# PMUIO_BLOCK.net
KiCad netlist of a schematic drawn in Altium Designer
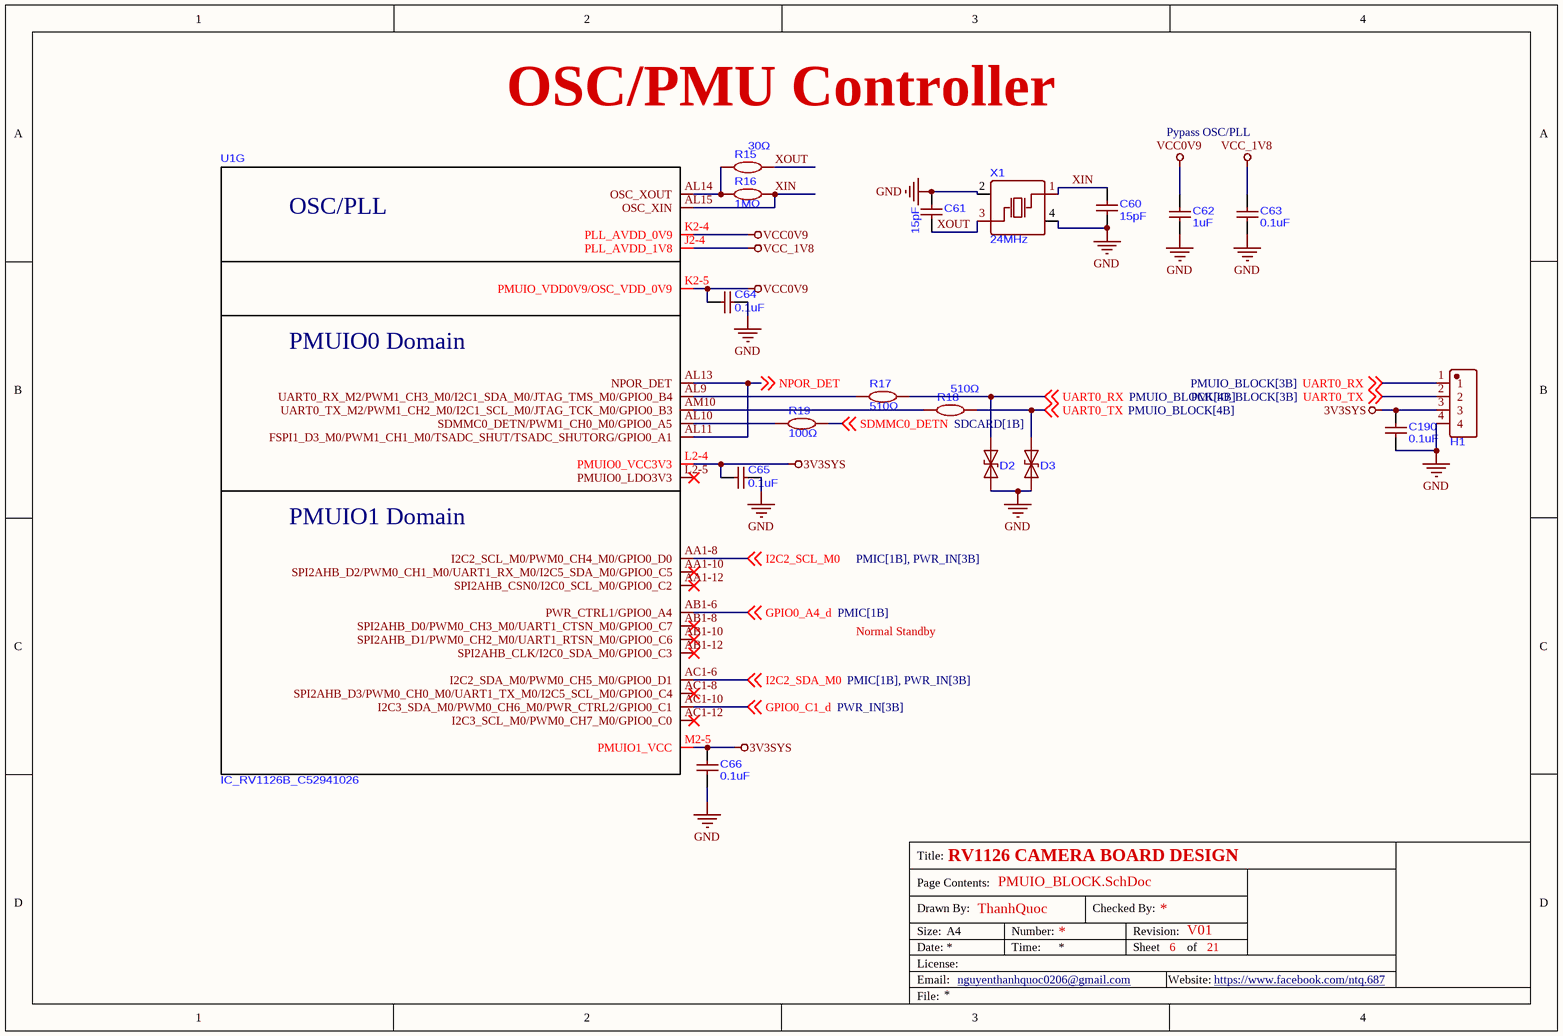
[diagram p0: PMUIO_BLOCK.SchDoc]

(export (version "E")
  (design (tool "Eeschema 10.0.6"))
  (components
    (comp (ref "C60")
      (value "15pF")
      (footprint "C0201")
      (description "CAP CER 15pF 50V NP0 0201")
      (libsource (lib "Schlib1") (part "CAP_15pF-25V-5%-0201"))
    )
    (comp (ref "C61")
      (value "15pF")
      (footprint "C0201")
      (description "CAP CER 15pF 50V NP0 0201")
      (libsource (lib "Schlib1") (part "CAP_15pF-25V-5%-0201"))
    )
    (comp (ref "C62")
      (value "1uF")
      (footprint "C0201")
      (description "1uF ±10% 6.3V Ceramic Capacitor X5R 0201")
      (libsource (lib "Schlib1") (part "CAP_1uF-6.3V-10%-0201"))
    )
    (comp (ref "C63")
      (value "0.1uF")
      (footprint "C0201")
      (description "0.1uF ±10% 6.3V Ceramic Capacitor X5R 0201")
      (libsource (lib "Schlib1") (part "CAP_100nF-6.3V-10%-0201_1"))
    )
    (comp (ref "C64")
      (value "0.1uF")
      (footprint "C0201")
      (description "0.1uF ±10% 6.3V Ceramic Capacitor X5R 0201")
      (libsource (lib "Schlib1") (part "CAP_100nF-6.3V-10%-0201_1"))
    )
    (comp (ref "C65")
      (value "0.1uF")
      (footprint "C0201")
      (description "0.1uF ±10% 6.3V Ceramic Capacitor X5R 0201")
      (libsource (lib "Schlib1") (part "CAP_100nF-6.3V-10%-0201_1"))
    )
    (comp (ref "C66")
      (value "0.1uF")
      (footprint "C0201")
      (description "0.1uF ±10% 6.3V Ceramic Capacitor X5R 0201")
      (libsource (lib "Schlib1") (part "CAP_100nF-6.3V-10%-0201_1"))
    )
    (comp (ref "C190")
      (value "0.1uF")
      (footprint "C0201")
      (description "0.1uF ±10% 6.3V Ceramic Capacitor X5R 0201")
      (libsource (lib "Schlib1") (part "CAP_100nF-6.3V-10%-0201_1"))
    )
    (comp (ref "D2")
      (value "ESD DIODE")
      (footprint "DSN0603-2_L0.7-W0.3-P0.40-BI")
      (description "ESD DIODE 5VWM 5VC DSN0603-2 0.13PF")
      (libsource (lib "Schlib1") (part "PESD5V0H1BSFYL"))
    )
    (comp (ref "D3")
      (value "ESD DIODE")
      (footprint "DSN0603-2_L0.7-W0.3-P0.40-BI")
      (description "ESD DIODE 5VWM 5VC DSN0603-2 0.13PF")
      (libsource (lib "Schlib1") (part "PESD5V0H1BSFYL"))
    )
    (comp (ref "H1")
      (value "Through Hole,P=1.27mm")
      (footprint "HDR-TH_4P-P1.27-V-M")
      (libsource (lib "Schlib1") (part "PZ127V-11-04-0720"))
    )
    (comp (ref "R15")
      (value "30Ω")
      (footprint "R0201")
      (description "RES 30Ω ±1% 50mW 0201")
      (libsource (lib "Schlib1") (part "RES_30Ω-0.05W-1%-0201"))
    )
    (comp (ref "R16")
      (value "1MΩ")
      (footprint "R0201")
      (description "RES 1MΩ ±5% 50mW 0201")
      (libsource (lib "Schlib1") (part "RES_1M-0.1W-5%-0201"))
    )
    (comp (ref "R17")
      (value "510Ω")
      (footprint "R0201")
      (description "510Ω 50mW 25V Thick Film Resistor ±200ppm/℃ ±1% 0201 Chip Resistor - Surface Mount RoHS")
      (libsource (lib "Schlib1") (part "RES_510-0.05W-1%-0201"))
    )
    (comp (ref "R18")
      (value "510Ω")
      (footprint "R0201")
      (description "510Ω 50mW 25V Thick Film Resistor ±200ppm/℃ ±1% 0201 Chip Resistor - Surface Mount RoHS")
      (libsource (lib "Schlib1") (part "RES_510-0.05W-1%-0201"))
    )
    (comp (ref "R19")
      (value "100Ω")
      (footprint "R0201")
      (description "RES 100Ω ±1% 50mW 0201")
      (libsource (lib "Schlib1") (part "RES_100OHM-50mW-1%-0201"))
    )
    (comp (ref "U1")
      (value "IC_RV1126B_C52941026")
      (footprint "CCSP-491_L14.0-W14.0-TL_RV1126B")
      (libsource (lib "Schlib1") (part "IC_RV1126B_C52941026"))
    )
    (comp (ref "X1")
      (value "24MHz")
      (footprint "CRYSTAL-SMD_4P-L2.0-W1.6-BL")
      (description "CRYSTAL 24MHz 12pF SMD")
      (libsource (lib "Schlib1") (part "XTAL_24Mhz-12pF-4-SMD"))
    )
  )
  (nets
    (net (code "1") (name "/XIN") (class "Default")
      (node (ref "C60") (pin "2") (pinfunction "2_2") (pintype "passive"))
      (node (ref "R16") (pin "2") (pinfunction "2_2") (pintype "passive"))
      (node (ref "U1") (pin "AL15") (pinfunction "OSC_XIN_AL15") (pintype "passive"))
      (node (ref "X1") (pin "1") (pinfunction "OSC1_1") (pintype "passive"))
    )
    (net (code "2") (name "/XOUT") (class "Default")
      (node (ref "C61") (pin "1") (pinfunction "1_1") (pintype "passive"))
      (node (ref "R15") (pin "2") (pinfunction "2_2") (pintype "passive"))
      (node (ref "X1") (pin "3") (pinfunction "OSC2_3") (pintype "passive"))
    )
    (net (code "3") (name "3V3SYS") (class "Default")
      (node (ref "C190") (pin "2") (pinfunction "2_2") (pintype "passive"))
      (node (ref "C65") (pin "2") (pinfunction "2_2") (pintype "passive"))
      (node (ref "C66") (pin "2") (pinfunction "2_2") (pintype "passive"))
      (node (ref "H1") (pin "3") (pinfunction "3_3") (pintype "passive"))
      (node (ref "U1") (pin "L2-4") (pinfunction "PMUIO0_VCC3V3_L2-4") (pintype "passive"))
      (node (ref "U1") (pin "M2-5") (pinfunction "PMUIO1_VCC_M2-5") (pintype "passive"))
    )
    (net (code "4") (name "GND") (class "Default")
      (node (ref "C190") (pin "1") (pinfunction "1_1") (pintype "passive"))
      (node (ref "C60") (pin "1") (pinfunction "1_1") (pintype "passive"))
      (node (ref "C61") (pin "2") (pinfunction "2_2") (pintype "passive"))
      (node (ref "C62") (pin "1") (pinfunction "1_1") (pintype "passive"))
      (node (ref "C63") (pin "1") (pinfunction "1_1") (pintype "passive"))
      (node (ref "C64") (pin "1") (pinfunction "1_1") (pintype "passive"))
      (node (ref "C65") (pin "1") (pinfunction "1_1") (pintype "passive"))
      (node (ref "C66") (pin "1") (pinfunction "1_1") (pintype "passive"))
      (node (ref "D2") (pin "1") (pinfunction "K_1") (pintype "passive"))
      (node (ref "D3") (pin "1") (pinfunction "K_1") (pintype "passive"))
      (node (ref "H1") (pin "4") (pinfunction "4_4") (pintype "passive"))
      (node (ref "X1") (pin "2") (pinfunction "GND_2") (pintype "passive"))
      (node (ref "X1") (pin "4") (pinfunction "GND_4") (pintype "passive"))
    )
    (net (code "5") (name "GPIO0_A4_d") (class "Default")
      (node (ref "U1") (pin "AB1-6") (pinfunction "PWR_CTRL1/GPIO0_A4_AB1-6") (pintype "passive"))
    )
    (net (code "6") (name "GPIO0_C1_d") (class "Default")
      (node (ref "U1") (pin "AC1-10") (pinfunction "I2C3_SDA_M0/PWM0_CH6_M0/PWR_CTRL2/GPIO0_C1_AC1-10") (pintype "passive"))
    )
    (net (code "7") (name "I2C2_SCL_M0") (class "Default")
      (node (ref "U1") (pin "AA1-8") (pinfunction "I2C2_SCL_M0/PWM0_CH4_M0/GPIO0_D0_AA1-8") (pintype "passive"))
    )
    (net (code "8") (name "I2C2_SDA_M0") (class "Default")
      (node (ref "U1") (pin "AC1-6") (pinfunction "I2C2_SDA_M0/PWM0_CH5_M0/GPIO0_D1_AC1-6") (pintype "passive"))
    )
    (net (code "9") (name "NPOR_DET") (class "Default")
      (node (ref "U1") (pin "AL11") (pinfunction "FSPI1_D3_M0/PWM1_CH1_M0/TSADC_SHUT/TSADC_SHUTORG/GPIO0_A1_AL11") (pintype "passive"))
      (node (ref "U1") (pin "AL13") (pinfunction "NPOR_DET_AL13") (pintype "passive"))
    )
    (net (code "10") (name "Net-(U1G-OSC_XOUT)") (class "Default")
      (node (ref "R15") (pin "1") (pinfunction "1_1") (pintype "passive"))
      (node (ref "R16") (pin "1") (pinfunction "1_1") (pintype "passive"))
      (node (ref "U1") (pin "AL14") (pinfunction "OSC_XOUT_AL14") (pintype "passive"))
    )
    (net (code "11") (name "Net-(U1G-SDMMC0_DETN{slash}PWM1_CH0_M0{slash}GPIO0_A5)") (class "Default")
      (node (ref "R19") (pin "1") (pinfunction "1_1") (pintype "passive"))
      (node (ref "U1") (pin "AL10") (pinfunction "SDMMC0_DETN/PWM1_CH0_M0/GPIO0_A5_AL10") (pintype "passive"))
    )
    (net (code "12") (name "Net-(U1G-UART0_RX_M2{slash}PWM1_CH3_M0{slash}I2C1_SDA_M0{slash}JTAG_TMS_M0{slash}GPIO0_B4)") (class "Default")
      (node (ref "R17") (pin "1") (pinfunction "1_1") (pintype "passive"))
      (node (ref "U1") (pin "AL9") (pinfunction "UART0_RX_M2/PWM1_CH3_M0/I2C1_SDA_M0/JTAG_TMS_M0/GPIO0_B4_AL9") (pintype "passive"))
    )
    (net (code "13") (name "Net-(U1G-UART0_TX_M2{slash}PWM1_CH2_M0{slash}I2C1_SCL_M0{slash}JTAG_TCK_M0{slash}GPIO0_B3)") (class "Default")
      (node (ref "R18") (pin "1") (pinfunction "1_1") (pintype "passive"))
      (node (ref "U1") (pin "AM10") (pinfunction "UART0_TX_M2/PWM1_CH2_M0/I2C1_SCL_M0/JTAG_TCK_M0/GPIO0_B3_AM10") (pintype "passive"))
    )
    (net (code "14") (name "SDMMC0_DETN") (class "Default")
      (node (ref "R19") (pin "2") (pinfunction "2_2") (pintype "passive"))
    )
    (net (code "15") (name "UART0_RX") (class "Default")
      (node (ref "D2") (pin "2") (pinfunction "A_2") (pintype "passive"))
      (node (ref "H1") (pin "1") (pinfunction "1_1") (pintype "passive"))
      (node (ref "R17") (pin "2") (pinfunction "2_2") (pintype "passive"))
    )
    (net (code "16") (name "UART0_TX") (class "Default")
      (node (ref "D3") (pin "2") (pinfunction "A_2") (pintype "passive"))
      (node (ref "H1") (pin "2") (pinfunction "2_2") (pintype "passive"))
      (node (ref "R18") (pin "2") (pinfunction "2_2") (pintype "passive"))
    )
    (net (code "17") (name "VCC0V9") (class "Default")
      (node (ref "C62") (pin "2") (pinfunction "2_2") (pintype "passive"))
      (node (ref "C64") (pin "2") (pinfunction "2_2") (pintype "passive"))
      (node (ref "U1") (pin "K2-4") (pinfunction "PLL_AVDD_0V9_K2-4") (pintype "passive"))
      (node (ref "U1") (pin "K2-5") (pinfunction "PMUIO_VDD0V9/OSC_VDD_0V9_K2-5") (pintype "passive"))
    )
    (net (code "18") (name "VCC_1V8") (class "Default")
      (node (ref "C63") (pin "2") (pinfunction "2_2") (pintype "passive"))
      (node (ref "U1") (pin "J2-4") (pinfunction "PLL_AVDD_1V8_J2-4") (pintype "passive"))
    )
    (net (code "19") (name "unconnected-(U1G-I2C3_SCL_M0{slash}PWM0_CH7_M0{slash}GPIO0_C0-PadAC1-12)") (class "Default")
      (node (ref "U1") (pin "AC1-12") (pinfunction "I2C3_SCL_M0/PWM0_CH7_M0/GPIO0_C0_AC1-12") (pintype "passive+no_connect"))
    )
    (net (code "20") (name "unconnected-(U1G-PMUIO0_LDO3V3-PadL2-5)") (class "Default")
      (node (ref "U1") (pin "L2-5") (pinfunction "PMUIO0_LDO3V3_L2-5") (pintype "passive+no_connect"))
    )
    (net (code "21") (name "unconnected-(U1G-SPI2AHB_CLK{slash}I2C0_SDA_M0{slash}GPIO0_C3-PadAB1-12)") (class "Default")
      (node (ref "U1") (pin "AB1-12") (pinfunction "SPI2AHB_CLK/I2C0_SDA_M0/GPIO0_C3_AB1-12") (pintype "passive+no_connect"))
    )
    (net (code "22") (name "unconnected-(U1G-SPI2AHB_CSN0{slash}I2C0_SCL_M0{slash}GPIO0_C2-PadAA1-12)") (class "Default")
      (node (ref "U1") (pin "AA1-12") (pinfunction "SPI2AHB_CSN0/I2C0_SCL_M0/GPIO0_C2_AA1-12") (pintype "passive+no_connect"))
    )
    (net (code "23") (name "unconnected-(U1G-SPI2AHB_D0{slash}PWM0_CH3_M0{slash}UART1_CTSN_M0{slash}GPIO0_C7-PadAB1-8)") (class "Default")
      (node (ref "U1") (pin "AB1-8") (pinfunction "SPI2AHB_D0/PWM0_CH3_M0/UART1_CTSN_M0/GPIO0_C7_AB1-8") (pintype "passive+no_connect"))
    )
    (net (code "24") (name "unconnected-(U1G-SPI2AHB_D1{slash}PWM0_CH2_M0{slash}UART1_RTSN_M0{slash}GPIO0_C6-PadAB1-10)") (class "Default")
      (node (ref "U1") (pin "AB1-10") (pinfunction "SPI2AHB_D1/PWM0_CH2_M0/UART1_RTSN_M0/GPIO0_C6_AB1-10") (pintype "passive+no_connect"))
    )
    (net (code "25") (name "unconnected-(U1G-SPI2AHB_D2{slash}PWM0_CH1_M0{slash}UART1_RX_M0{slash}I2C5_SDA_M0{slash}GPIO0_C5-PadAA1-10)") (class "Default")
      (node (ref "U1") (pin "AA1-10") (pinfunction "SPI2AHB_D2/PWM0_CH1_M0/UART1_RX_M0/I2C5_SDA_M0/GPIO0_C5_AA1-10") (pintype "passive+no_connect"))
    )
    (net (code "26") (name "unconnected-(U1G-SPI2AHB_D3{slash}PWM0_CH0_M0{slash}UART1_TX_M0{slash}I2C5_SCL_M0{slash}GPIO0_C4-PadAC1-8)") (class "Default")
      (node (ref "U1") (pin "AC1-8") (pinfunction "SPI2AHB_D3/PWM0_CH0_M0/UART1_TX_M0/I2C5_SCL_M0/GPIO0_C4_AC1-8") (pintype "passive+no_connect"))
    )
  )
)
